# pmon_uno.net
KiCad netlist of a schematic drawn in EAGLE
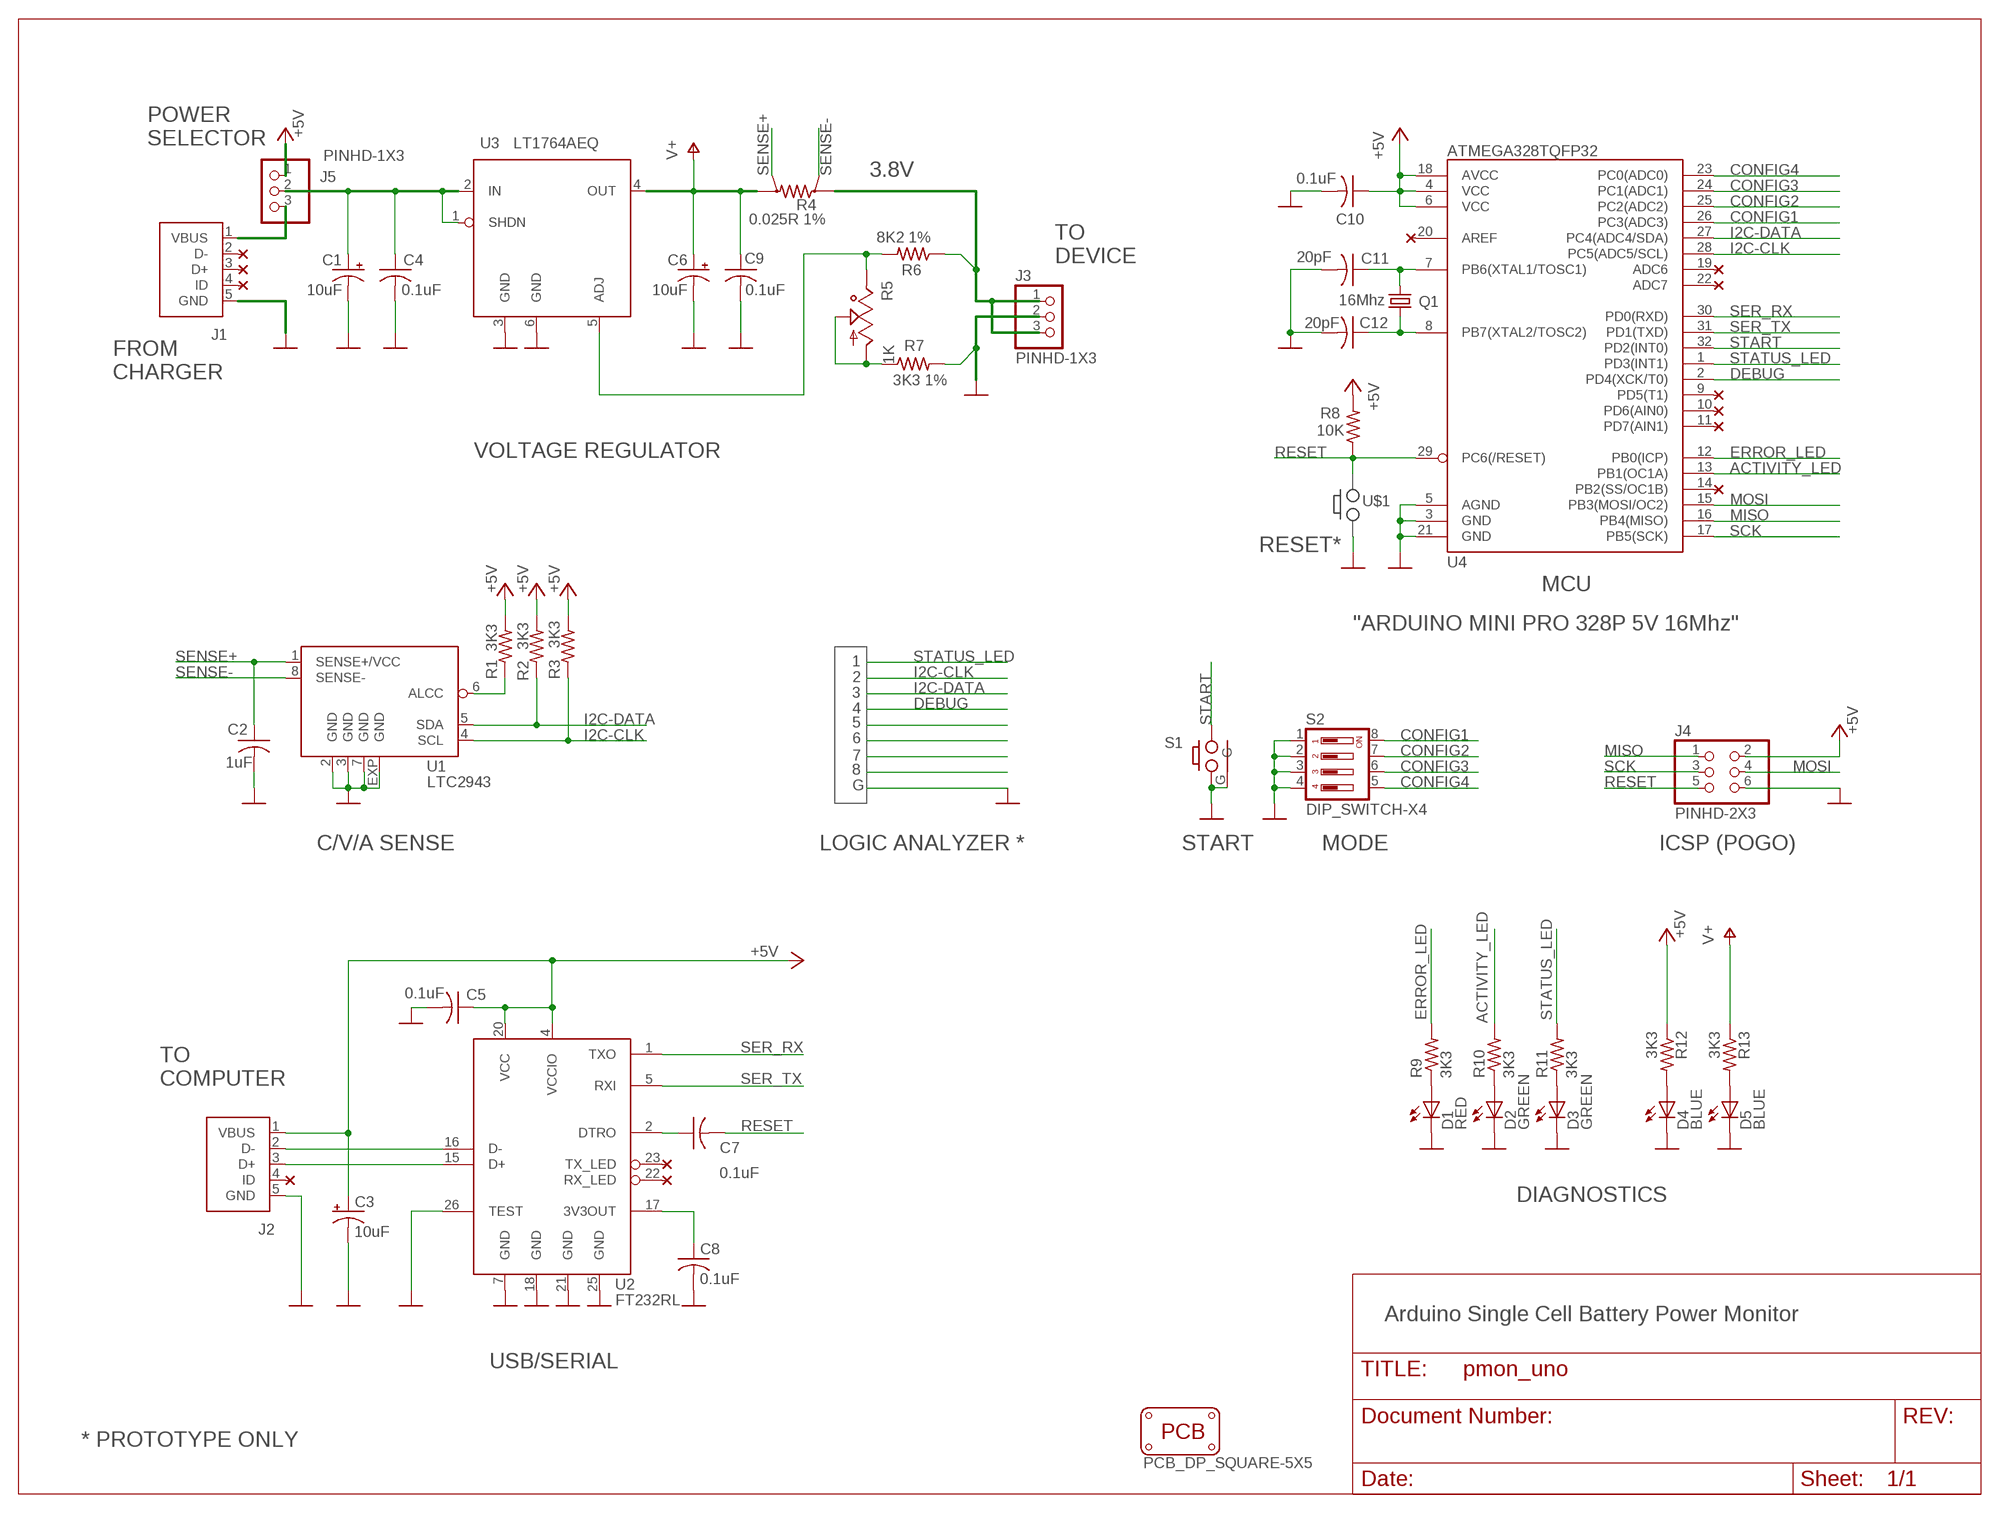
[diagram p0: schematic, sheet 1]

(export (version "E")
  (design (tool "Eeschema 10.0.6"))
  (components
    (comp (ref "C1")
      (value "10uF")
      (footprint "eagle-import:A_3216-18R")
      (libsource (lib "eagle-import") (part "CPOL-USA/3216-18R"))
    )
    (comp (ref "C2")
      (value "1uF")
      (footprint "eagle-import:C0603")
      (libsource (lib "eagle-import") (part "CAP-C0603"))
    )
    (comp (ref "C3")
      (value "10uF")
      (footprint "eagle-import:A_3216-18R")
      (libsource (lib "eagle-import") (part "CPOL-USA/3216-18R"))
    )
    (comp (ref "C4")
      (value "0.1uF")
      (footprint "eagle-import:C0603")
      (libsource (lib "eagle-import") (part "CAP-C0603"))
    )
    (comp (ref "C5")
      (value "0.1uF")
      (footprint "eagle-import:C0603")
      (libsource (lib "eagle-import") (part "CAP-C0603"))
    )
    (comp (ref "C6")
      (value "10uF")
      (footprint "eagle-import:A_3216-18R")
      (libsource (lib "eagle-import") (part "CPOL-USA/3216-18R"))
    )
    (comp (ref "C7")
      (value "0.1uF")
      (footprint "eagle-import:C0603")
      (libsource (lib "eagle-import") (part "CAP-C0603"))
    )
    (comp (ref "C8")
      (value "0.1uF")
      (footprint "eagle-import:C0603")
      (libsource (lib "eagle-import") (part "CAP-C0603"))
    )
    (comp (ref "C9")
      (value "0.1uF")
      (footprint "eagle-import:C0603")
      (libsource (lib "eagle-import") (part "CAP-C0603"))
    )
    (comp (ref "C10")
      (value "0.1uF")
      (footprint "eagle-import:C0603")
      (libsource (lib "eagle-import") (part "CAP-C0603"))
    )
    (comp (ref "C11")
      (value "20pF")
      (footprint "eagle-import:C0603")
      (libsource (lib "eagle-import") (part "CAP-C0603"))
    )
    (comp (ref "C12")
      (value "20pF")
      (footprint "eagle-import:C0603")
      (libsource (lib "eagle-import") (part "CAP-C0603"))
    )
    (comp (ref "D1")
      (value "RED")
      (footprint "eagle-import:1206-LED")
      (libsource (lib "eagle-import") (part "LED1206"))
    )
    (comp (ref "D2")
      (value "GREEN")
      (footprint "eagle-import:1206-LED")
      (libsource (lib "eagle-import") (part "LED1206"))
    )
    (comp (ref "D3")
      (value "GREEN")
      (footprint "eagle-import:1206-LED")
      (libsource (lib "eagle-import") (part "LED1206"))
    )
    (comp (ref "D4")
      (value "BLUE")
      (footprint "eagle-import:1206-LED")
      (libsource (lib "eagle-import") (part "LED1206"))
    )
    (comp (ref "D5")
      (value "BLUE")
      (footprint "eagle-import:1206-LED")
      (libsource (lib "eagle-import") (part "LED1206"))
    )
    (comp (ref "J1")
      (value "USB")
      (footprint "eagle-import:USB-MICRO-ZX62RD-AB-5P8")
      (libsource (lib "eagle-import") (part "USB"))
    )
    (comp (ref "J2")
      (value "USB")
      (footprint "eagle-import:USB-MICRO-ZX62RD-AB-5P8")
      (libsource (lib "eagle-import") (part "USB"))
    )
    (comp (ref "J3")
      (value "PINHD-1X3")
      (footprint "eagle-import:1X03")
      (libsource (lib "eagle-import") (part "PINHD-1X3"))
    )
    (comp (ref "J4")
      (value "PINHD-2X3")
      (footprint "eagle-import:2X03")
      (libsource (lib "eagle-import") (part "PINHD-2X3"))
    )
    (comp (ref "J5")
      (value "PINHD-1X3")
      (footprint "eagle-import:1X03")
      (libsource (lib "eagle-import") (part "PINHD-1X3"))
    )
    (comp (ref "PCB1")
      (value "PCB_DP_SQUARE-5X5")
      (footprint "eagle-import:DP5050_V1")
      (libsource (lib "eagle-import") (part "PCB_DP_SQUARE-5X5"))
    )
    (comp (ref "Q1")
      (value "16Mhz")
      (footprint "eagle-import:CRYSTAL-CTS406")
      (libsource (lib "eagle-import") (part "CRYSTALCTS406"))
    )
    (comp (ref "R1")
      (value "3K3")
      (footprint "eagle-import:R0603")
      (libsource (lib "eagle-import") (part "RES-R0603"))
    )
    (comp (ref "R2")
      (value "3K3")
      (footprint "eagle-import:R0603")
      (libsource (lib "eagle-import") (part "RES-R0603"))
    )
    (comp (ref "R3")
      (value "3K3")
      (footprint "eagle-import:R0603")
      (libsource (lib "eagle-import") (part "RES-R0603"))
    )
    (comp (ref "R4")
      (value "0.025R 1%")
      (footprint "eagle-import:KELVIN-6432")
      (libsource (lib "eagle-import") (part "RES-SHUNT-6432"))
    )
    (comp (ref "R5")
      (value "1K")
      (footprint "eagle-import:TRIM-POT_SM-42_43A")
      (libsource (lib "eagle-import") (part "TRIM_US-SM-42/43A"))
    )
    (comp (ref "R6")
      (value "8K2 1%")
      (footprint "eagle-import:R0603")
      (libsource (lib "eagle-import") (part "RES-R0603"))
    )
    (comp (ref "R7")
      (value "3K3 1%")
      (footprint "eagle-import:R0603")
      (libsource (lib "eagle-import") (part "RES-R0603"))
    )
    (comp (ref "R8")
      (value "10K")
      (footprint "eagle-import:R0603")
      (libsource (lib "eagle-import") (part "RES-R0603"))
    )
    (comp (ref "R9")
      (value "3K3")
      (footprint "eagle-import:R0603")
      (libsource (lib "eagle-import") (part "RES-R0603"))
    )
    (comp (ref "R10")
      (value "3K3")
      (footprint "eagle-import:R0603")
      (libsource (lib "eagle-import") (part "RES-R0603"))
    )
    (comp (ref "R11")
      (value "3K3")
      (footprint "eagle-import:R0603")
      (libsource (lib "eagle-import") (part "RES-R0603"))
    )
    (comp (ref "R12")
      (value "3K3")
      (footprint "eagle-import:R0603")
      (libsource (lib "eagle-import") (part "RES-R0603"))
    )
    (comp (ref "R13")
      (value "3K3")
      (footprint "eagle-import:R0603")
      (libsource (lib "eagle-import") (part "RES-R0603"))
    )
    (comp (ref "S1")
      (value "PUSH_BUTTON_SHIELDED")
      (footprint "eagle-import:TLE1105")
      (libsource (lib "eagle-import") (part "PUSH_BUTTON_SHIELDED"))
    )
    (comp (ref "S2")
      (value "DIP_SWITCH-X4")
      (footprint "eagle-import:DIP-SWITCH-X4")
      (libsource (lib "eagle-import") (part "DIP_SWITCH-X4"))
    )
    (comp (ref "U1")
      (value "LTC2943")
      (footprint "eagle-import:DFN8-3X3")
      (libsource (lib "eagle-import") (part "LTC2943"))
    )
    (comp (ref "U2")
      (value "FT232RL")
      (footprint "eagle-import:SSOP28DB")
      (libsource (lib "eagle-import") (part "FT232RL"))
    )
    (comp (ref "U3")
      (value "LT1764AEQ")
      (footprint "eagle-import:TO263-5")
      (libsource (lib "eagle-import") (part "LTE1764"))
    )
    (comp (ref "U4")
      (value "ATMEGA328TQFP32")
      (footprint "eagle-import:TQFP32-08")
      (libsource (lib "eagle-import") (part "ATMEGA328TQFP32"))
    )
  )
  (nets
    (net (code "1") (name "+5V") (class "Default")
      (node (ref "C10") (pin "1") (pinfunction "1_1") (pintype "passive"))
      (node (ref "C3") (pin "+") (pinfunction "+_+") (pintype "passive"))
      (node (ref "C5") (pin "1") (pinfunction "1_1") (pintype "passive"))
      (node (ref "J2") (pin "1") (pinfunction "VBUS_1") (pintype "bidirectional"))
      (node (ref "J4") (pin "2") (pinfunction "2_2") (pintype "passive"))
      (node (ref "J5") (pin "1") (pinfunction "1_1") (pintype "passive"))
      (node (ref "R1") (pin "2") (pinfunction "2_2") (pintype "passive"))
      (node (ref "R12") (pin "1") (pinfunction "1_1") (pintype "passive"))
      (node (ref "R2") (pin "2") (pinfunction "2_2") (pintype "passive"))
      (node (ref "R3") (pin "2") (pinfunction "2_2") (pintype "passive"))
      (node (ref "R8") (pin "2") (pinfunction "2_2") (pintype "passive"))
      (node (ref "U2") (pin "20") (pinfunction "VCC_20") (pintype "power_in"))
      (node (ref "U2") (pin "4") (pinfunction "VCCIO_4") (pintype "power_in"))
      (node (ref "U4") (pin "18") (pinfunction "AVCC_18") (pintype "power_in"))
      (node (ref "U4") (pin "4") (pinfunction "VCC_4") (pintype "power_in"))
      (node (ref "U4") (pin "6") (pinfunction "VCC_6") (pintype "power_in"))
    )
    (net (code "2") (name "/ACTIVITY_LED") (class "Default")
      (node (ref "R10") (pin "2") (pinfunction "2_2") (pintype "passive"))
      (node (ref "U4") (pin "13") (pinfunction "PB1(OC1A)_13") (pintype "bidirectional"))
    )
    (net (code "3") (name "/AREF") (class "Default")
      (node (ref "U4") (pin "20") (pinfunction "AREF_20") (pintype "power_in"))
    )
    (net (code "4") (name "/CONFIG1") (class "Default")
      (node (ref "S2") (pin "8") (pinfunction "8_8") (pintype "passive"))
      (node (ref "U4") (pin "26") (pinfunction "PC3(ADC3)_26") (pintype "bidirectional"))
    )
    (net (code "5") (name "/CONFIG2") (class "Default")
      (node (ref "S2") (pin "7") (pinfunction "7_7") (pintype "passive"))
      (node (ref "U4") (pin "25") (pinfunction "PC2(ADC2)_25") (pintype "bidirectional"))
    )
    (net (code "6") (name "/CONFIG3") (class "Default")
      (node (ref "S2") (pin "6") (pinfunction "6_6") (pintype "passive"))
      (node (ref "U4") (pin "24") (pinfunction "PC1(ADC1)_24") (pintype "bidirectional"))
    )
    (net (code "7") (name "/CONFIG4") (class "Default")
      (node (ref "S2") (pin "5") (pinfunction "5_5") (pintype "passive"))
      (node (ref "U4") (pin "23") (pinfunction "PC0(ADC0)_23") (pintype "bidirectional"))
    )
    (net (code "8") (name "/DEBUG") (class "Default")
      (node (ref "U4") (pin "2") (pinfunction "PD4(XCK/T0)_2") (pintype "bidirectional"))
    )
    (net (code "9") (name "/ERROR_LED") (class "Default")
      (node (ref "R9") (pin "2") (pinfunction "2_2") (pintype "passive"))
      (node (ref "U4") (pin "12") (pinfunction "PB0(ICP)_12") (pintype "bidirectional"))
    )
    (net (code "10") (name "/I2C-CLK") (class "Default")
      (node (ref "R3") (pin "1") (pinfunction "1_1") (pintype "passive"))
      (node (ref "U1") (pin "4") (pinfunction "SCL_4") (pintype "input"))
      (node (ref "U4") (pin "28") (pinfunction "PC5(ADC5/SCL)_28") (pintype "bidirectional"))
    )
    (net (code "11") (name "/I2C-DATA") (class "Default")
      (node (ref "R2") (pin "1") (pinfunction "1_1") (pintype "passive"))
      (node (ref "U1") (pin "5") (pinfunction "SDA_5") (pintype "bidirectional"))
      (node (ref "U4") (pin "27") (pinfunction "PC4(ADC4/SDA)_27") (pintype "bidirectional"))
    )
    (net (code "12") (name "/MISO") (class "Default")
      (node (ref "J4") (pin "1") (pinfunction "1_1") (pintype "passive"))
      (node (ref "U4") (pin "16") (pinfunction "PB4(MISO)_16") (pintype "bidirectional"))
    )
    (net (code "13") (name "/MOSI") (class "Default")
      (node (ref "J4") (pin "4") (pinfunction "4_4") (pintype "passive"))
      (node (ref "U4") (pin "15") (pinfunction "PB3(MOSI/OC2)_15") (pintype "bidirectional"))
    )
    (net (code "14") (name "/RESET") (class "Default")
      (node (ref "C7") (pin "2") (pinfunction "2_2") (pintype "passive"))
      (node (ref "J4") (pin "5") (pinfunction "5_5") (pintype "passive"))
      (node (ref "R8") (pin "1") (pinfunction "1_1") (pintype "passive"))
      (node (ref "U4") (pin "29") (pinfunction "PC6(/RESET)_29") (pintype "bidirectional"))
    )
    (net (code "15") (name "/SCK") (class "Default")
      (node (ref "J4") (pin "3") (pinfunction "3_3") (pintype "passive"))
      (node (ref "U4") (pin "17") (pinfunction "PB5(SCK)_17") (pintype "bidirectional"))
    )
    (net (code "16") (name "/SENSE+") (class "Default")
      (node (ref "C2") (pin "1") (pinfunction "1_1") (pintype "passive"))
      (node (ref "R4") (pin "V2") (pinfunction "V2_V2") (pintype "passive"))
      (node (ref "U1") (pin "1") (pinfunction "SENSE+/VCC_1") (pintype "passive"))
    )
    (net (code "17") (name "/SENSE-") (class "Default")
      (node (ref "R4") (pin "V1") (pinfunction "V1_V1") (pintype "passive"))
      (node (ref "U1") (pin "8") (pinfunction "SENSE-_8") (pintype "passive"))
    )
    (net (code "18") (name "/SER_RX") (class "Default")
      (node (ref "U2") (pin "1") (pinfunction "TXO_1") (pintype "output"))
      (node (ref "U4") (pin "30") (pinfunction "PD0(RXD)_30") (pintype "bidirectional"))
    )
    (net (code "19") (name "/SER_TX") (class "Default")
      (node (ref "U2") (pin "5") (pinfunction "RXI_5") (pintype "input"))
      (node (ref "U4") (pin "31") (pinfunction "PD1(TXD)_31") (pintype "bidirectional"))
    )
    (net (code "20") (name "/START") (class "Default")
      (node (ref "S1") (pin "B") (pinfunction "2_B") (pintype "passive"))
      (node (ref "U4") (pin "32") (pinfunction "PD2(INT0)_32") (pintype "bidirectional"))
    )
    (net (code "21") (name "/STATUS_LED") (class "Default")
      (node (ref "R11") (pin "2") (pinfunction "2_2") (pintype "passive"))
      (node (ref "U4") (pin "1") (pinfunction "PD3(INT1)_1") (pintype "bidirectional"))
    )
    (net (code "22") (name "GND") (class "Default")
      (node (ref "C1") (pin "-") (pinfunction "-_-") (pintype "passive"))
      (node (ref "C10") (pin "2") (pinfunction "2_2") (pintype "passive"))
      (node (ref "C11") (pin "2") (pinfunction "2_2") (pintype "passive"))
      (node (ref "C12") (pin "2") (pinfunction "2_2") (pintype "passive"))
      (node (ref "C2") (pin "2") (pinfunction "2_2") (pintype "passive"))
      (node (ref "C3") (pin "-") (pinfunction "-_-") (pintype "passive"))
      (node (ref "C4") (pin "2") (pinfunction "2_2") (pintype "passive"))
      (node (ref "C5") (pin "2") (pinfunction "2_2") (pintype "passive"))
      (node (ref "C6") (pin "-") (pinfunction "-_-") (pintype "passive"))
      (node (ref "C8") (pin "2") (pinfunction "2_2") (pintype "passive"))
      (node (ref "C9") (pin "2") (pinfunction "2_2") (pintype "passive"))
      (node (ref "D1") (pin "C") (pinfunction "C_C") (pintype "passive"))
      (node (ref "D2") (pin "C") (pinfunction "C_C") (pintype "passive"))
      (node (ref "D3") (pin "C") (pinfunction "C_C") (pintype "passive"))
      (node (ref "D4") (pin "C") (pinfunction "C_C") (pintype "passive"))
      (node (ref "D5") (pin "C") (pinfunction "C_C") (pintype "passive"))
      (node (ref "J1") (pin "5") (pinfunction "GND_5") (pintype "bidirectional"))
      (node (ref "J2") (pin "5") (pinfunction "GND_5") (pintype "bidirectional"))
      (node (ref "J3") (pin "2") (pinfunction "2_2") (pintype "passive"))
      (node (ref "J4") (pin "6") (pinfunction "6_6") (pintype "passive"))
      (node (ref "R7") (pin "2") (pinfunction "2_2") (pintype "passive"))
      (node (ref "S1") (pin "A") (pinfunction "1_A") (pintype "passive"))
      (node (ref "S1") (pin "G") (pinfunction "G_G") (pintype "bidirectional"))
      (node (ref "S2") (pin "1") (pinfunction "1_1") (pintype "passive"))
      (node (ref "S2") (pin "2") (pinfunction "2_2") (pintype "passive"))
      (node (ref "S2") (pin "3") (pinfunction "3_3") (pintype "passive"))
      (node (ref "S2") (pin "4") (pinfunction "4_4") (pintype "passive"))
      (node (ref "U1") (pin "2") (pinfunction "GND_2") (pintype "power_in"))
      (node (ref "U1") (pin "3") (pinfunction "GND_3") (pintype "power_in"))
      (node (ref "U1") (pin "7") (pinfunction "GND_7") (pintype "power_in"))
      (node (ref "U1") (pin "EXP") (pinfunction "GND_EXP") (pintype "power_in"))
      (node (ref "U2") (pin "18") (pinfunction "GND_18") (pintype "power_in"))
      (node (ref "U2") (pin "21") (pinfunction "GND_21") (pintype "power_in"))
      (node (ref "U2") (pin "25") (pinfunction "GND_25") (pintype "power_in"))
      (node (ref "U2") (pin "26") (pinfunction "TEST_26") (pintype "input"))
      (node (ref "U2") (pin "7") (pinfunction "GND_7") (pintype "power_in"))
      (node (ref "U3") (pin "3") (pinfunction "GND_3") (pintype "bidirectional"))
      (node (ref "U3") (pin "6") (pinfunction "GND_6") (pintype "bidirectional"))
      (node (ref "U4") (pin "21") (pinfunction "GND_21") (pintype "power_in"))
      (node (ref "U4") (pin "3") (pinfunction "GND_3") (pintype "power_in"))
      (node (ref "U4") (pin "5") (pinfunction "AGND_5") (pintype "power_in"))
    )
    (net (code "23") (name "Net-(D1-PadA)") (class "Default")
      (node (ref "D1") (pin "A") (pinfunction "A_A") (pintype "passive"))
      (node (ref "R9") (pin "1") (pinfunction "1_1") (pintype "passive"))
    )
    (net (code "24") (name "Net-(D2-PadA)") (class "Default")
      (node (ref "D2") (pin "A") (pinfunction "A_A") (pintype "passive"))
      (node (ref "R10") (pin "1") (pinfunction "1_1") (pintype "passive"))
    )
    (net (code "25") (name "Net-(D3-PadA)") (class "Default")
      (node (ref "D3") (pin "A") (pinfunction "A_A") (pintype "passive"))
      (node (ref "R11") (pin "1") (pinfunction "1_1") (pintype "passive"))
    )
    (net (code "26") (name "Net-(D4-PadA)") (class "Default")
      (node (ref "D4") (pin "A") (pinfunction "A_A") (pintype "passive"))
      (node (ref "R12") (pin "2") (pinfunction "2_2") (pintype "passive"))
    )
    (net (code "27") (name "Net-(D5-PadA)") (class "Default")
      (node (ref "D5") (pin "A") (pinfunction "A_A") (pintype "passive"))
      (node (ref "R13") (pin "2") (pinfunction "2_2") (pintype "passive"))
    )
    (net (code "28") (name "Net-(J1-VBUS)") (class "Default")
      (node (ref "J1") (pin "1") (pinfunction "VBUS_1") (pintype "bidirectional"))
      (node (ref "J5") (pin "3") (pinfunction "3_3") (pintype "passive"))
    )
    (net (code "29") (name "Net-(J2-D+)") (class "Default")
      (node (ref "J2") (pin "3") (pinfunction "D+_3") (pintype "bidirectional"))
      (node (ref "U2") (pin "15") (pinfunction "D+_15") (pintype "passive"))
    )
    (net (code "30") (name "Net-(J2-D-)") (class "Default")
      (node (ref "J2") (pin "2") (pinfunction "D-_2") (pintype "bidirectional"))
      (node (ref "U2") (pin "16") (pinfunction "D-_16") (pintype "passive"))
    )
    (net (code "31") (name "Net-(J3-Pad1)") (class "Default")
      (node (ref "J3") (pin "1") (pinfunction "1_1") (pintype "passive"))
      (node (ref "J3") (pin "3") (pinfunction "3_3") (pintype "passive"))
      (node (ref "R4") (pin "I1") (pinfunction "I1_I1") (pintype "passive"))
      (node (ref "R6") (pin "1") (pinfunction "1_1") (pintype "passive"))
    )
    (net (code "32") (name "Net-(Q1-2)") (class "Default")
      (node (ref "C12") (pin "1") (pinfunction "1_1") (pintype "passive"))
      (node (ref "Q1") (pin "3") (pinfunction "2_3") (pintype "passive"))
      (node (ref "U4") (pin "8") (pinfunction "PB7(XTAL2/TOSC2)_8") (pintype "bidirectional"))
    )
    (net (code "33") (name "Net-(R5-Pad1)") (class "Default")
      (node (ref "R5") (pin "1") (pinfunction "1_1") (pintype "passive"))
      (node (ref "R5") (pin "2") (pinfunction "2_2") (pintype "passive"))
      (node (ref "R7") (pin "1") (pinfunction "1_1") (pintype "passive"))
    )
    (net (code "34") (name "Net-(U1-ALCC)") (class "Default")
      (node (ref "R1") (pin "1") (pinfunction "1_1") (pintype "passive"))
      (node (ref "U1") (pin "6") (pinfunction "ALCC_6") (pintype "open_collector"))
    )
    (net (code "35") (name "Net-(U2-3V3OUT)") (class "Default")
      (node (ref "C8") (pin "1") (pinfunction "1_1") (pintype "passive"))
      (node (ref "U2") (pin "17") (pinfunction "3V3OUT_17") (pintype "power_in"))
    )
    (net (code "36") (name "Net-(U2-DTRO)") (class "Default")
      (node (ref "C7") (pin "1") (pinfunction "1_1") (pintype "passive"))
      (node (ref "U2") (pin "2") (pinfunction "DTRO_2") (pintype "output"))
    )
    (net (code "37") (name "Net-(U3-ADJ)") (class "Default")
      (node (ref "R5") (pin "3") (pinfunction "3_3") (pintype "passive"))
      (node (ref "R6") (pin "2") (pinfunction "2_2") (pintype "passive"))
      (node (ref "U3") (pin "5") (pinfunction "ADJ_5") (pintype "bidirectional"))
    )
    (net (code "38") (name "Net-(U3-IN)") (class "Default")
      (node (ref "C1") (pin "+") (pinfunction "+_+") (pintype "passive"))
      (node (ref "C4") (pin "1") (pinfunction "1_1") (pintype "passive"))
      (node (ref "J5") (pin "2") (pinfunction "2_2") (pintype "passive"))
      (node (ref "U3") (pin "1") (pinfunction "SHDN_1") (pintype "bidirectional"))
      (node (ref "U3") (pin "2") (pinfunction "IN_2") (pintype "bidirectional"))
    )
    (net (code "39") (name "Net-(U4-PB6(XTAL1{slash}TOSC1))") (class "Default")
      (node (ref "C11") (pin "1") (pinfunction "1_1") (pintype "passive"))
      (node (ref "Q1") (pin "1") (pinfunction "1_1") (pintype "passive"))
      (node (ref "U4") (pin "7") (pinfunction "PB6(XTAL1/TOSC1)_7") (pintype "bidirectional"))
    )
    (net (code "40") (name "V+") (class "Default")
      (node (ref "C6") (pin "+") (pinfunction "+_+") (pintype "passive"))
      (node (ref "C9") (pin "1") (pinfunction "1_1") (pintype "passive"))
      (node (ref "R13") (pin "1") (pinfunction "1_1") (pintype "passive"))
      (node (ref "R4") (pin "I2") (pinfunction "I2_I2") (pintype "passive"))
      (node (ref "U3") (pin "4") (pinfunction "OUT_4") (pintype "bidirectional"))
    )
    (net (code "41") (name "unconnected-(J1-D+-Pad3)") (class "Default")
      (node (ref "J1") (pin "3") (pinfunction "D+_3") (pintype "bidirectional"))
    )
    (net (code "42") (name "unconnected-(J1-D--Pad2)") (class "Default")
      (node (ref "J1") (pin "2") (pinfunction "D-_2") (pintype "bidirectional"))
    )
    (net (code "43") (name "unconnected-(J1-ID-Pad4)") (class "Default")
      (node (ref "J1") (pin "4") (pinfunction "ID_4") (pintype "bidirectional"))
    )
    (net (code "44") (name "unconnected-(J2-ID-Pad4)") (class "Default")
      (node (ref "J2") (pin "4") (pinfunction "ID_4") (pintype "bidirectional"))
    )
    (net (code "45") (name "unconnected-(U2-RX_LED-Pad22)") (class "Default")
      (node (ref "U2") (pin "22") (pinfunction "RX_LED_22") (pintype "output"))
    )
    (net (code "46") (name "unconnected-(U2-TX_LED-Pad23)") (class "Default")
      (node (ref "U2") (pin "23") (pinfunction "TX_LED_23") (pintype "output"))
    )
    (net (code "47") (name "unconnected-(U4-ADC6-Pad19)") (class "Default")
      (node (ref "U4") (pin "19") (pinfunction "ADC6_19") (pintype "bidirectional"))
    )
    (net (code "48") (name "unconnected-(U4-ADC7-Pad22)") (class "Default")
      (node (ref "U4") (pin "22") (pinfunction "ADC7_22") (pintype "bidirectional"))
    )
    (net (code "49") (name "unconnected-(U4-PB2(SS{slash}OC1B)-Pad14)") (class "Default")
      (node (ref "U4") (pin "14") (pinfunction "PB2(SS/OC1B)_14") (pintype "bidirectional"))
    )
    (net (code "50") (name "unconnected-(U4-PD5(T1)-Pad9)") (class "Default")
      (node (ref "U4") (pin "9") (pinfunction "PD5(T1)_9") (pintype "bidirectional"))
    )
    (net (code "51") (name "unconnected-(U4-PD6(AIN0)-Pad10)") (class "Default")
      (node (ref "U4") (pin "10") (pinfunction "PD6(AIN0)_10") (pintype "bidirectional"))
    )
    (net (code "52") (name "unconnected-(U4-PD7(AIN1)-Pad11)") (class "Default")
      (node (ref "U4") (pin "11") (pinfunction "PD7(AIN1)_11") (pintype "bidirectional"))
    )
  )
)
